# fridge.net
KiCad netlist of a schematic drawn in EAGLE
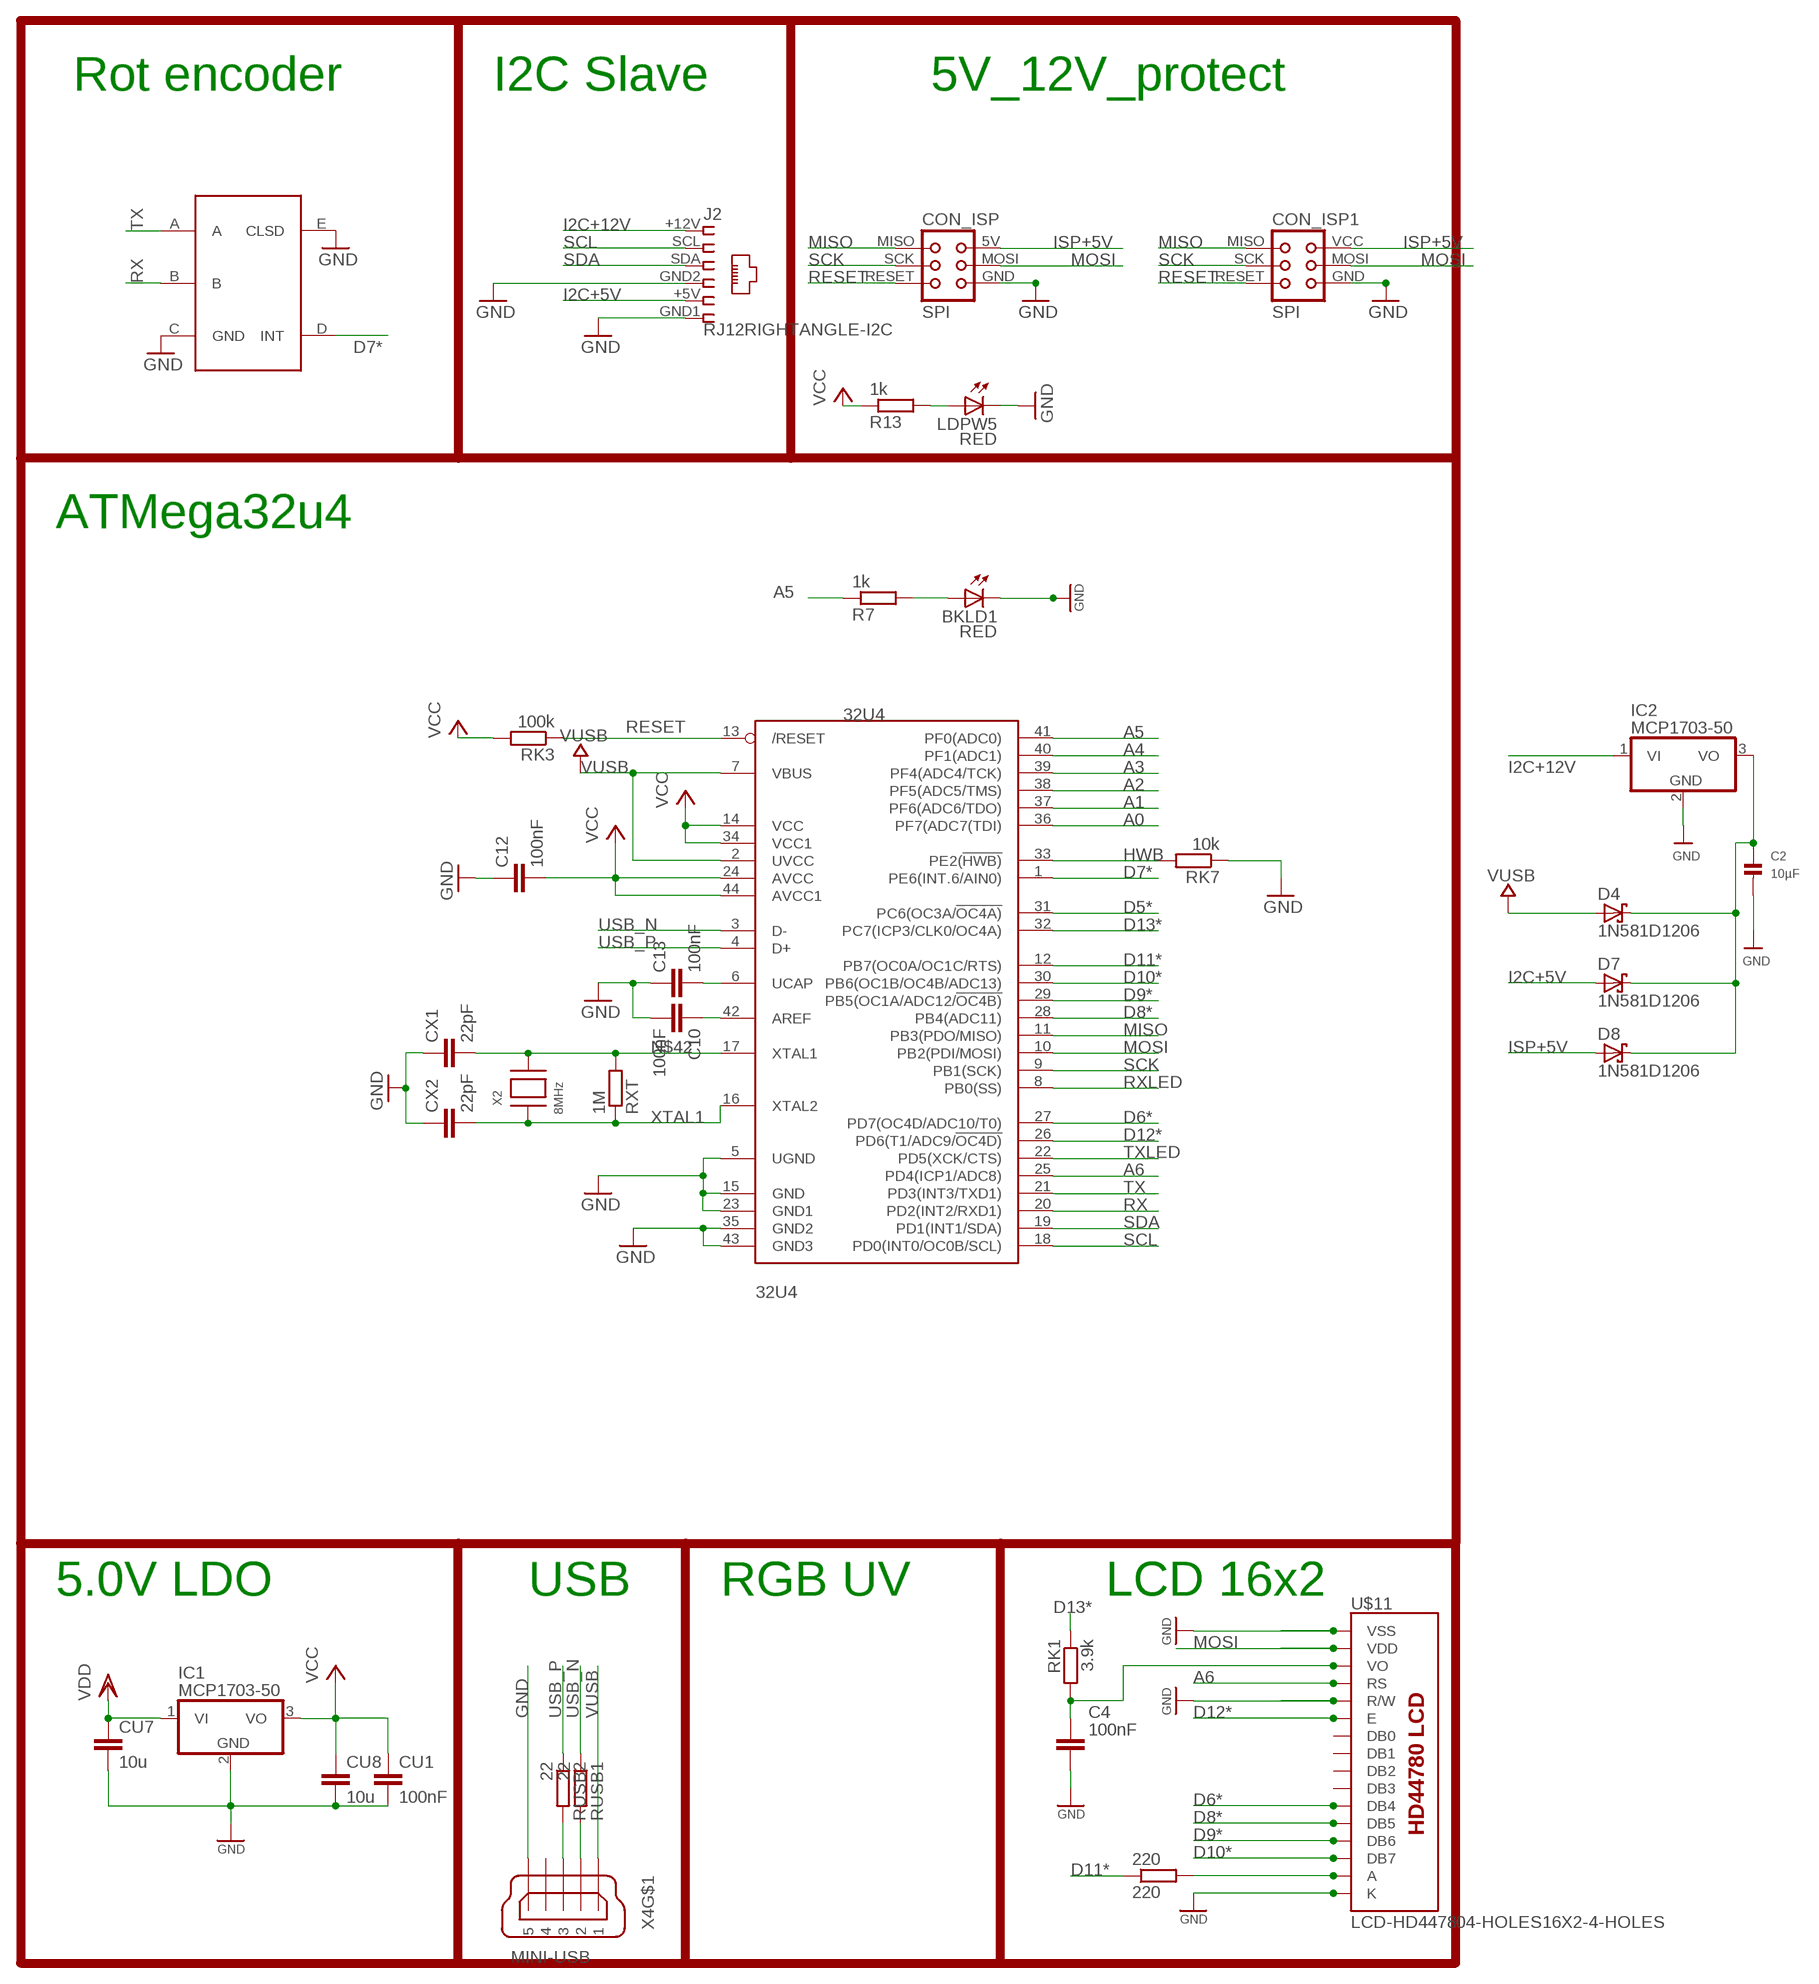
[diagram p0: schematic, sheet 1]

(export (version "E")
  (design (tool "Eeschema 10.0.6"))
  (components
    (comp (ref "32U4")
      (value "32U4")
      (footprint "eagle-import:TQFP44")
      (libsource (lib "eagle-import") (part "ATMEGA32U4-AU"))
    )
    (comp (ref "220")
      (value "220")
      (footprint "eagle-import:R0805")
      (libsource (lib "eagle-import") (part "R-EU_R0805"))
    )
    (comp (ref "BKLD1")
      (value "RED")
      (footprint "eagle-import:CHIP-LED0805")
      (libsource (lib "eagle-import") (part "LEDCHIP-LED0805"))
    )
    (comp (ref "C2")
      (value "10µF")
      (footprint "eagle-import:0805")
      (libsource (lib "eagle-import") (part "CAP_CERAMIC0805"))
    )
    (comp (ref "C4")
      (value "100nF")
      (footprint "eagle-import:C805")
      (libsource (lib "eagle-import") (part "CAPACITOR_NPOL-0805"))
    )
    (comp (ref "C10")
      (value "100nF")
      (footprint "eagle-import:C1206")
      (libsource (lib "eagle-import") (part "C-EUC1206"))
    )
    (comp (ref "C12")
      (value "100nF")
      (footprint "eagle-import:C1206")
      (libsource (lib "eagle-import") (part "C-EUC1206"))
    )
    (comp (ref "C13")
      (value "100nF")
      (footprint "eagle-import:C1206")
      (libsource (lib "eagle-import") (part "C-EUC1206"))
    )
    (comp (ref "CON_ISP")
      (value "SPI")
      (footprint "eagle-import:TC2030-MCP-NL")
      (libsource (lib "eagle-import") (part "TINYISPT"))
    )
    (comp (ref "CON_ISP1")
      (value "SPI")
      (footprint "eagle-import:TINYISP")
      (libsource (lib "eagle-import") (part "TINYISP"))
    )
    (comp (ref "CU1")
      (value "100nF")
      (footprint "eagle-import:C0805")
      (libsource (lib "eagle-import") (part "C-EUC0805"))
    )
    (comp (ref "CU7")
      (value "10u")
      (footprint "eagle-import:C0805")
      (libsource (lib "eagle-import") (part "C-EUC0805"))
    )
    (comp (ref "CU8")
      (value "10u")
      (footprint "eagle-import:C0805")
      (libsource (lib "eagle-import") (part "C-EUC0805"))
    )
    (comp (ref "CX1")
      (value "22pF")
      (footprint "eagle-import:C1206")
      (libsource (lib "eagle-import") (part "C-EUC1206"))
    )
    (comp (ref "CX2")
      (value "22pF")
      (footprint "eagle-import:C1206")
      (libsource (lib "eagle-import") (part "C-EUC1206"))
    )
    (comp (ref "D4")
      (value "1N581D1206")
      (footprint "eagle-import:LED-1206")
      (libsource (lib "eagle-import") (part "1N581D1206"))
    )
    (comp (ref "D7")
      (value "1N581D1206")
      (footprint "eagle-import:LED-1206")
      (libsource (lib "eagle-import") (part "1N581D1206"))
    )
    (comp (ref "D8")
      (value "1N581D1206")
      (footprint "eagle-import:LED-1206")
      (libsource (lib "eagle-import") (part "1N581D1206"))
    )
    (comp (ref "IC1")
      (value "MCP1703-50")
      (footprint "eagle-import:SOT223")
      (libsource (lib "eagle-import") (part "MCP1703DB"))
    )
    (comp (ref "IC2")
      (value "MCP1703-50")
      (footprint "eagle-import:SOT223")
      (libsource (lib "eagle-import") (part "MCP1703DB"))
    )
    (comp (ref "J2")
      (value "RJ12RIGHTANGLE-I2C")
      (footprint "eagle-import:RJ12-RIGHTANGLE-I2C")
      (libsource (lib "eagle-import") (part "RJ12RIGHTANGLE-I2C"))
    )
    (comp (ref "LDPW5")
      (value "RED")
      (footprint "eagle-import:CHIP-LED0805")
      (libsource (lib "eagle-import") (part "LEDCHIP-LED0805"))
    )
    (comp (ref "R7")
      (value "1k")
      (footprint "eagle-import:R0805")
      (libsource (lib "eagle-import") (part "R-EU_R0805"))
    )
    (comp (ref "R13")
      (value "1k")
      (footprint "eagle-import:R0805")
      (libsource (lib "eagle-import") (part "resistor_R-EU_R0805"))
    )
    (comp (ref "RK1")
      (value "3.9k")
      (footprint "eagle-import:R0805")
      (libsource (lib "eagle-import") (part "R-EU_R0805"))
    )
    (comp (ref "RK3")
      (value "100k")
      (footprint "eagle-import:M0805")
      (libsource (lib "eagle-import") (part "resistor_R-EU_M0805"))
    )
    (comp (ref "RK7")
      (value "10k")
      (footprint "eagle-import:M0805")
      (libsource (lib "eagle-import") (part "resistor_R-EU_M0805"))
    )
    (comp (ref "RUSB1")
      (value "22")
      (footprint "eagle-import:M1206")
      (libsource (lib "eagle-import") (part "resistor_R-EU_M1206"))
    )
    (comp (ref "RUSB2")
      (value "22")
      (footprint "eagle-import:M1206")
      (libsource (lib "eagle-import") (part "resistor_R-EU_M1206"))
    )
    (comp (ref "RXT")
      (value "1M")
      (footprint "eagle-import:R0805")
      (libsource (lib "eagle-import") (part "R-EU_R0805"))
    )
    (comp (ref "U$1")
      (value "EC11E")
      (footprint "eagle-import:EC11E")
      (libsource (lib "eagle-import") (part "EC11E"))
    )
    (comp (ref "U$11")
      (value "LCD-HD447804-HOLES16X2-4-HOLES")
      (footprint "eagle-import:LCD-16X2-4HOLES")
      (libsource (lib "eagle-import") (part "LCD-HD4478016X2-4-HOLES4-HOLES"))
    )
    (comp (ref "X2")
      (value "8MHz")
      (footprint "eagle-import:NX6035")
      (libsource (lib "eagle-import") (part "XTALNX6035"))
    )
    (comp (ref "X4")
      (value "MINI-USB")
      (footprint "eagle-import:32005-201")
      (libsource (lib "eagle-import") (part "MINI-USB-SCHIELD-32005-201"))
    )
  )
  (nets
    (net (code "1") (name "/A0") (class "Default")
      (node (ref "32U4") (pin "36") (pinfunction "PF7(ADC7(TDI)_36") (pintype "bidirectional"))
    )
    (net (code "2") (name "/A1") (class "Default")
      (node (ref "32U4") (pin "37") (pinfunction "PF6(ADC6/TDO)_37") (pintype "bidirectional"))
    )
    (net (code "3") (name "/A2") (class "Default")
      (node (ref "32U4") (pin "38") (pinfunction "PF5(ADC5/TMS)_38") (pintype "bidirectional"))
    )
    (net (code "4") (name "/A3") (class "Default")
      (node (ref "32U4") (pin "39") (pinfunction "PF4(ADC4/TCK)_39") (pintype "bidirectional"))
    )
    (net (code "5") (name "/A4") (class "Default")
      (node (ref "32U4") (pin "40") (pinfunction "PF1(ADC1)_40") (pintype "bidirectional"))
    )
    (net (code "6") (name "/A5") (class "Default")
      (node (ref "32U4") (pin "41") (pinfunction "PF0(ADC0)_41") (pintype "bidirectional"))
      (node (ref "R7") (pin "1") (pinfunction "1_1") (pintype "passive"))
    )
    (net (code "7") (name "/A6") (class "Default")
      (node (ref "32U4") (pin "25") (pinfunction "PD4(ICP1/ADC8)_25") (pintype "bidirectional"))
      (node (ref "U$11") (pin "4") (pinfunction "RS_4") (pintype "input"))
    )
    (net (code "8") (name "/D5*") (class "Default")
      (node (ref "32U4") (pin "31") (pinfunction "PC6(OC3A/~{OC4A})_31") (pintype "bidirectional"))
    )
    (net (code "9") (name "/D6*") (class "Default")
      (node (ref "32U4") (pin "27") (pinfunction "PD7(OC4D/ADC10/T0)_27") (pintype "bidirectional"))
      (node (ref "U$11") (pin "11") (pinfunction "DB4_11") (pintype "bidirectional"))
    )
    (net (code "10") (name "/D7*") (class "Default")
      (node (ref "32U4") (pin "1") (pinfunction "PE6(INT.6/AIN0)_1") (pintype "bidirectional"))
      (node (ref "U$1") (pin "D") (pinfunction "INT_D") (pintype "bidirectional"))
    )
    (net (code "11") (name "/D8*") (class "Default")
      (node (ref "32U4") (pin "28") (pinfunction "PB4(ADC11)_28") (pintype "bidirectional"))
      (node (ref "U$11") (pin "12") (pinfunction "DB5_12") (pintype "bidirectional"))
    )
    (net (code "12") (name "/D9*") (class "Default")
      (node (ref "32U4") (pin "29") (pinfunction "PB5(OC1A/ADC12/~{OC4B})_29") (pintype "bidirectional"))
      (node (ref "U$11") (pin "13") (pinfunction "DB6_13") (pintype "bidirectional"))
    )
    (net (code "13") (name "/D10*") (class "Default")
      (node (ref "32U4") (pin "30") (pinfunction "PB6(OC1B/OC4B/ADC13)_30") (pintype "bidirectional"))
      (node (ref "U$11") (pin "14") (pinfunction "DB7_14") (pintype "bidirectional"))
    )
    (net (code "14") (name "/D11*") (class "Default")
      (node (ref "220") (pin "1") (pinfunction "1_1") (pintype "passive"))
      (node (ref "32U4") (pin "12") (pinfunction "PB7(OC0A/OC1C/RTS)_12") (pintype "bidirectional"))
    )
    (net (code "15") (name "/D12*") (class "Default")
      (node (ref "32U4") (pin "26") (pinfunction "PD6(T1/ADC9/~{OC4D})_26") (pintype "bidirectional"))
      (node (ref "U$11") (pin "6") (pinfunction "E_6") (pintype "input"))
    )
    (net (code "16") (name "/D13*") (class "Default")
      (node (ref "32U4") (pin "32") (pinfunction "PC7(ICP3/CLK0/OC4A)_32") (pintype "bidirectional"))
      (node (ref "RK1") (pin "1") (pinfunction "1_1") (pintype "passive"))
    )
    (net (code "17") (name "/HWB") (class "Default")
      (node (ref "32U4") (pin "33") (pinfunction "PE2(~{HWB})_33") (pintype "bidirectional"))
      (node (ref "RK7") (pin "2") (pinfunction "2_2") (pintype "passive"))
    )
    (net (code "18") (name "/I2C+5V") (class "Default")
      (node (ref "D7") (pin "A") (pinfunction "A_A") (pintype "passive"))
      (node (ref "J2") (pin "+5V") (pinfunction "5_+5V") (pintype "bidirectional"))
    )
    (net (code "19") (name "/I2C+12V") (class "Default")
      (node (ref "IC2") (pin "1") (pinfunction "VI_1") (pintype "input"))
      (node (ref "J2") (pin "+12V") (pinfunction "1_+12V") (pintype "bidirectional"))
    )
    (net (code "20") (name "/ISP+5V") (class "Default")
      (node (ref "CON_ISP") (pin "5V") (pinfunction "VCC_5V") (pintype "passive"))
      (node (ref "CON_ISP1") (pin "VCC") (pinfunction "VCC_VCC") (pintype "passive"))
      (node (ref "D8") (pin "A") (pinfunction "A_A") (pintype "passive"))
    )
    (net (code "21") (name "/MISO") (class "Default")
      (node (ref "32U4") (pin "11") (pinfunction "PB3(PDO/MISO)_11") (pintype "bidirectional"))
      (node (ref "CON_ISP") (pin "MISO") (pinfunction "MISO_MISO") (pintype "passive"))
      (node (ref "CON_ISP1") (pin "MISO") (pinfunction "MISO_MISO") (pintype "passive"))
    )
    (net (code "22") (name "/MOSI") (class "Default")
      (node (ref "32U4") (pin "10") (pinfunction "PB2(PDI/MOSI)_10") (pintype "bidirectional"))
      (node (ref "CON_ISP") (pin "MOSI") (pinfunction "MOSI_MOSI") (pintype "passive"))
      (node (ref "CON_ISP1") (pin "MOSI") (pinfunction "MOSI_MOSI") (pintype "passive"))
      (node (ref "U$11") (pin "2") (pinfunction "VDD_2") (pintype "power_in"))
    )
    (net (code "23") (name "/N$42") (class "Default")
      (node (ref "32U4") (pin "17") (pinfunction "XTAL1_17") (pintype "bidirectional"))
      (node (ref "CX1") (pin "2") (pinfunction "2_2") (pintype "passive"))
      (node (ref "RXT") (pin "2") (pinfunction "2_2") (pintype "passive"))
      (node (ref "X2") (pin "P$2") (pinfunction "P$2_P$2") (pintype "bidirectional"))
    )
    (net (code "24") (name "/RESET") (class "Default")
      (node (ref "32U4") (pin "13") (pinfunction "/RESET_13") (pintype "bidirectional"))
      (node (ref "CON_ISP") (pin "RESET") (pinfunction "RESET_RESET") (pintype "passive"))
      (node (ref "CON_ISP1") (pin "RESET") (pinfunction "RESET_RESET") (pintype "passive"))
      (node (ref "RK3") (pin "1") (pinfunction "1_1") (pintype "passive"))
    )
    (net (code "25") (name "/RX") (class "Default")
      (node (ref "32U4") (pin "20") (pinfunction "PD2(INT2/RXD1)_20") (pintype "bidirectional"))
      (node (ref "U$1") (pin "B") (pinfunction "B_B") (pintype "bidirectional"))
    )
    (net (code "26") (name "/RXLED") (class "Default")
      (node (ref "32U4") (pin "8") (pinfunction "PB0(SS)_8") (pintype "bidirectional"))
    )
    (net (code "27") (name "/SCK") (class "Default")
      (node (ref "32U4") (pin "9") (pinfunction "PB1(SCK)_9") (pintype "bidirectional"))
      (node (ref "CON_ISP") (pin "SCK") (pinfunction "SCK_SCK") (pintype "passive"))
      (node (ref "CON_ISP1") (pin "SCK") (pinfunction "SCK_SCK") (pintype "passive"))
    )
    (net (code "28") (name "/SCL") (class "Default")
      (node (ref "32U4") (pin "18") (pinfunction "PD0(INT0/OC0B/SCL)_18") (pintype "bidirectional"))
      (node (ref "J2") (pin "SCL") (pinfunction "2_SCL") (pintype "bidirectional"))
    )
    (net (code "29") (name "/SDA") (class "Default")
      (node (ref "32U4") (pin "19") (pinfunction "PD1(INT1/SDA)_19") (pintype "bidirectional"))
      (node (ref "J2") (pin "SDA") (pinfunction "3_SDA") (pintype "bidirectional"))
    )
    (net (code "30") (name "/TX") (class "Default")
      (node (ref "32U4") (pin "21") (pinfunction "PD3(INT3/TXD1)_21") (pintype "bidirectional"))
      (node (ref "U$1") (pin "A") (pinfunction "A_A") (pintype "bidirectional"))
    )
    (net (code "31") (name "/TXLED") (class "Default")
      (node (ref "32U4") (pin "22") (pinfunction "PD5(XCK/CTS)_22") (pintype "bidirectional"))
    )
    (net (code "32") (name "/USB_N") (class "Default")
      (node (ref "32U4") (pin "3") (pinfunction "D-_3") (pintype "bidirectional"))
      (node (ref "RUSB1") (pin "1") (pinfunction "1_1") (pintype "passive"))
    )
    (net (code "33") (name "/USB_P") (class "Default")
      (node (ref "32U4") (pin "4") (pinfunction "D+_4") (pintype "bidirectional"))
      (node (ref "RUSB2") (pin "1") (pinfunction "1_1") (pintype "passive"))
    )
    (net (code "34") (name "/XTAL1") (class "Default")
      (node (ref "32U4") (pin "16") (pinfunction "XTAL2_16") (pintype "bidirectional"))
      (node (ref "CX2") (pin "2") (pinfunction "2_2") (pintype "passive"))
      (node (ref "RXT") (pin "1") (pinfunction "1_1") (pintype "passive"))
      (node (ref "X2") (pin "P$1") (pinfunction "P$1_P$1") (pintype "bidirectional"))
    )
    (net (code "35") (name "GND") (class "Default")
      (node (ref "32U4") (pin "15") (pinfunction "GND_15") (pintype "bidirectional"))
      (node (ref "32U4") (pin "23") (pinfunction "GND1_23") (pintype "bidirectional"))
      (node (ref "32U4") (pin "35") (pinfunction "GND2_35") (pintype "bidirectional"))
      (node (ref "32U4") (pin "43") (pinfunction "GND3_43") (pintype "bidirectional"))
      (node (ref "32U4") (pin "5") (pinfunction "UGND_5") (pintype "bidirectional"))
      (node (ref "BKLD1") (pin "C") (pinfunction "C_C") (pintype "passive"))
      (node (ref "C10") (pin "2") (pinfunction "2_2") (pintype "passive"))
      (node (ref "C12") (pin "1") (pinfunction "1_1") (pintype "passive"))
      (node (ref "C13") (pin "1") (pinfunction "1_1") (pintype "passive"))
      (node (ref "C2") (pin "2") (pinfunction "P$2_2") (pintype "passive"))
      (node (ref "C4") (pin "2") (pinfunction "2_2") (pintype "passive"))
      (node (ref "CON_ISP") (pin "GND") (pinfunction "GND_GND") (pintype "passive"))
      (node (ref "CON_ISP1") (pin "GND") (pinfunction "GND_GND") (pintype "passive"))
      (node (ref "CU1") (pin "2") (pinfunction "2_2") (pintype "passive"))
      (node (ref "CU7") (pin "2") (pinfunction "2_2") (pintype "passive"))
      (node (ref "CU8") (pin "2") (pinfunction "2_2") (pintype "passive"))
      (node (ref "CX1") (pin "1") (pinfunction "1_1") (pintype "passive"))
      (node (ref "CX2") (pin "1") (pinfunction "1_1") (pintype "passive"))
      (node (ref "IC1") (pin "2") (pinfunction "GND_2") (pintype "passive"))
      (node (ref "IC2") (pin "2") (pinfunction "GND_2") (pintype "passive"))
      (node (ref "J2") (pin "GND1") (pinfunction "6_GND1") (pintype "bidirectional"))
      (node (ref "J2") (pin "GND2") (pinfunction "4_GND2") (pintype "bidirectional"))
      (node (ref "LDPW5") (pin "C") (pinfunction "C_C") (pintype "passive"))
      (node (ref "RK7") (pin "1") (pinfunction "1_1") (pintype "passive"))
      (node (ref "U$1") (pin "C") (pinfunction "GND_C") (pintype "bidirectional"))
      (node (ref "U$1") (pin "E") (pinfunction "CLSD_E") (pintype "bidirectional"))
      (node (ref "U$11") (pin "1") (pinfunction "VSS_1") (pintype "power_in"))
      (node (ref "U$11") (pin "16") (pinfunction "K_16") (pintype "power_in"))
      (node (ref "U$11") (pin "5") (pinfunction "R/W_5") (pintype "input"))
      (node (ref "X4") (pin "5") (pinfunction "5_5") (pintype "passive"))
    )
    (net (code "36") (name "Net-(32U4-AREF)") (class "Default")
      (node (ref "32U4") (pin "42") (pinfunction "AREF_42") (pintype "bidirectional"))
      (node (ref "C10") (pin "1") (pinfunction "1_1") (pintype "passive"))
    )
    (net (code "37") (name "Net-(32U4-UCAP)") (class "Default")
      (node (ref "32U4") (pin "6") (pinfunction "UCAP_6") (pintype "bidirectional"))
      (node (ref "C13") (pin "2") (pinfunction "2_2") (pintype "passive"))
    )
    (net (code "38") (name "Net-(BKLD1-PadA)") (class "Default")
      (node (ref "BKLD1") (pin "A") (pinfunction "A_A") (pintype "passive"))
      (node (ref "R7") (pin "2") (pinfunction "2_2") (pintype "passive"))
    )
    (net (code "39") (name "Net-(C2-P$1)") (class "Default")
      (node (ref "C2") (pin "1") (pinfunction "P$1_1") (pintype "passive"))
      (node (ref "D4") (pin "C") (pinfunction "C_C") (pintype "passive"))
      (node (ref "D7") (pin "C") (pinfunction "C_C") (pintype "passive"))
      (node (ref "D8") (pin "C") (pinfunction "C_C") (pintype "passive"))
      (node (ref "IC2") (pin "3") (pinfunction "VO_3") (pintype "passive"))
    )
    (net (code "40") (name "Net-(LDPW5-PadA)") (class "Default")
      (node (ref "LDPW5") (pin "A") (pinfunction "A_A") (pintype "passive"))
      (node (ref "R13") (pin "2") (pinfunction "2_2") (pintype "passive"))
    )
    (net (code "41") (name "Net-(RUSB1-Pad2)") (class "Default")
      (node (ref "RUSB1") (pin "2") (pinfunction "2_2") (pintype "passive"))
      (node (ref "X4") (pin "2") (pinfunction "2_2") (pintype "passive"))
    )
    (net (code "42") (name "Net-(RUSB2-Pad2)") (class "Default")
      (node (ref "RUSB2") (pin "2") (pinfunction "2_2") (pintype "passive"))
      (node (ref "X4") (pin "3") (pinfunction "3_3") (pintype "passive"))
    )
    (net (code "43") (name "Net-(U$11-A)") (class "Default")
      (node (ref "220") (pin "2") (pinfunction "2_2") (pintype "passive"))
      (node (ref "U$11") (pin "15") (pinfunction "A_15") (pintype "power_in"))
    )
    (net (code "44") (name "Net-(U$11-VO)") (class "Default")
      (node (ref "C4") (pin "1") (pinfunction "1_1") (pintype "passive"))
      (node (ref "RK1") (pin "2") (pinfunction "2_2") (pintype "passive"))
      (node (ref "U$11") (pin "3") (pinfunction "VO_3") (pintype "bidirectional"))
    )
    (net (code "45") (name "VCC") (class "Default")
      (node (ref "32U4") (pin "14") (pinfunction "VCC_14") (pintype "bidirectional"))
      (node (ref "32U4") (pin "24") (pinfunction "AVCC_24") (pintype "bidirectional"))
      (node (ref "32U4") (pin "34") (pinfunction "VCC1_34") (pintype "bidirectional"))
      (node (ref "32U4") (pin "44") (pinfunction "AVCC1_44") (pintype "bidirectional"))
      (node (ref "C12") (pin "2") (pinfunction "2_2") (pintype "passive"))
      (node (ref "CU1") (pin "1") (pinfunction "1_1") (pintype "passive"))
      (node (ref "CU8") (pin "1") (pinfunction "1_1") (pintype "passive"))
      (node (ref "IC1") (pin "3") (pinfunction "VO_3") (pintype "passive"))
      (node (ref "R13") (pin "1") (pinfunction "1_1") (pintype "passive"))
      (node (ref "RK3") (pin "2") (pinfunction "2_2") (pintype "passive"))
    )
    (net (code "46") (name "VDD") (class "Default")
      (node (ref "CU7") (pin "1") (pinfunction "1_1") (pintype "passive"))
      (node (ref "IC1") (pin "1") (pinfunction "VI_1") (pintype "input"))
    )
    (net (code "47") (name "VUSB") (class "Default")
      (node (ref "32U4") (pin "2") (pinfunction "UVCC_2") (pintype "bidirectional"))
      (node (ref "32U4") (pin "7") (pinfunction "VBUS_7") (pintype "bidirectional"))
      (node (ref "D4") (pin "A") (pinfunction "A_A") (pintype "passive"))
      (node (ref "X4") (pin "1") (pinfunction "1_1") (pintype "passive"))
    )
    (net (code "48") (name "unconnected-(U$11-DB0-Pad7)") (class "Default")
      (node (ref "U$11") (pin "7") (pinfunction "DB0_7") (pintype "bidirectional"))
    )
    (net (code "49") (name "unconnected-(U$11-DB1-Pad8)") (class "Default")
      (node (ref "U$11") (pin "8") (pinfunction "DB1_8") (pintype "bidirectional"))
    )
    (net (code "50") (name "unconnected-(U$11-DB2-Pad9)") (class "Default")
      (node (ref "U$11") (pin "9") (pinfunction "DB2_9") (pintype "bidirectional"))
    )
    (net (code "51") (name "unconnected-(U$11-DB3-Pad10)") (class "Default")
      (node (ref "U$11") (pin "10") (pinfunction "DB3_10") (pintype "bidirectional"))
    )
    (net (code "52") (name "unconnected-(X4-Pad4)") (class "Default")
      (node (ref "X4") (pin "4") (pinfunction "4_4") (pintype "passive"))
    )
  )
)
